# machNguyenLy.net
KiCad netlist of a schematic drawn in Altium Designer
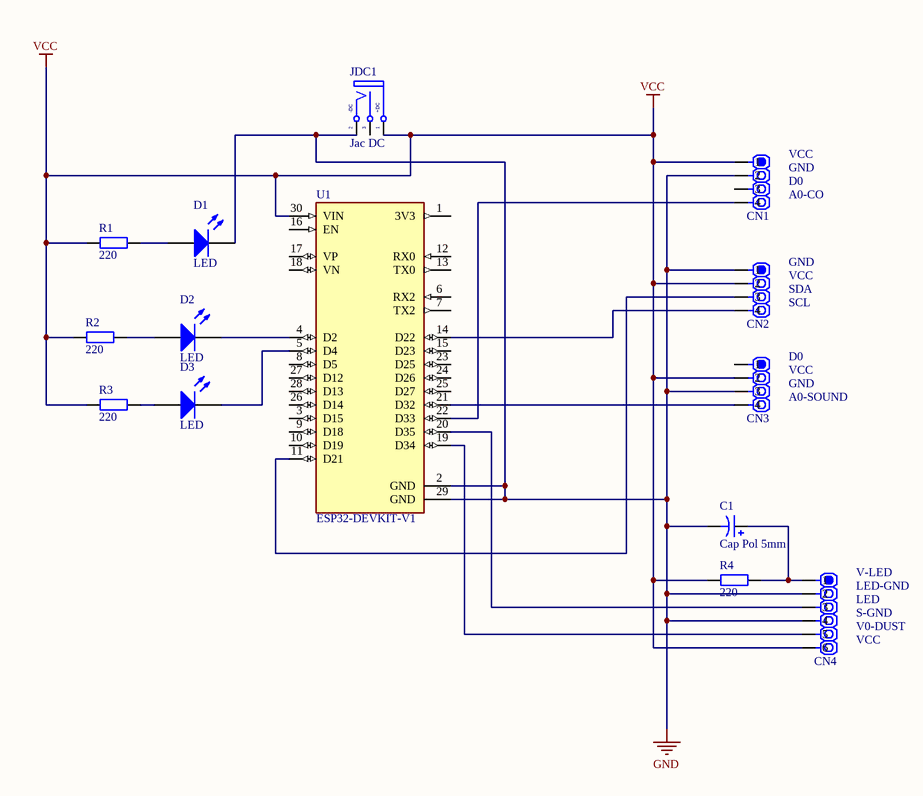
[diagram p0: machNguyenLy.SchDoc]

(export (version "E")
  (design (tool "Eeschema 10.0.6"))
  (components
    (comp (ref "C1")
      (value "Cap Pol 5mm")
      (footprint "C5mm")
      (description "Polarized Capacitor (Axial)")
      (fields (field (name "PUBLISHER") "Altium Limited"))
      (libsource (lib "hphonglib") (part "Cap Pol 5mm"))
    )
    (comp (ref "CN1")
      (value "IO")
      (footprint "CON.HDR1X4")
      (description "Header 1x4")
      (fields (field (name "PUBLISHER") "Hoang Nguyen"))
      (libsource (lib "hphonglib") (part "CON.HDR1x4"))
    )
    (comp (ref "CN2")
      (value "IO")
      (footprint "CON.HDR1X4")
      (description "Header 1x4")
      (fields (field (name "PUBLISHER") "Hoang Nguyen"))
      (libsource (lib "hphonglib") (part "CON.HDR1x4"))
    )
    (comp (ref "CN3")
      (value "IO")
      (footprint "CON.HDR1X4")
      (description "Header 1x4")
      (fields (field (name "PUBLISHER") "Hoang Nguyen"))
      (libsource (lib "hphonglib") (part "CON.HDR1x4"))
    )
    (comp (ref "CN4")
      (value "IO")
      (footprint "CON.HDR1X6")
      (description "Header 1x6")
      (fields (field (name "PUBLISHER") "Hoang Nguyen"))
      (libsource (lib "hphonglib") (part "CON.HDR1x6"))
    )
    (comp (ref "D1")
      (value "LED")
      (footprint "LED-0 5mm RED")
      (description "Typical LED")
      (fields (field (name "PUBLISHER") "Altium Limited"))
      (libsource (lib "hphonglib") (part "LED"))
    )
    (comp (ref "D2")
      (value "LED")
      (footprint "LED-0 5mm RED")
      (description "Typical LED")
      (fields (field (name "PUBLISHER") "Altium Limited"))
      (libsource (lib "hphonglib") (part "LED"))
    )
    (comp (ref "D3")
      (value "LED")
      (footprint "LED-0 5mm RED")
      (description "Typical LED")
      (fields (field (name "PUBLISHER") "Altium Limited"))
      (libsource (lib "hphonglib") (part "LED"))
    )
    (comp (ref "JDC1")
      (value "Jac DC")
      (footprint "DC-IN")
      (description "Jac DC input")
      (libsource (lib "hphonglib") (part "DCIN"))
    )
    (comp (ref "R1")
      (value "220")
      (footprint "R1/4W")
      (description "Resistor 1/4W")
      (libsource (lib "hphonglib") (part "R1/4W"))
    )
    (comp (ref "R2")
      (value "220")
      (footprint "R1/4W")
      (description "Resistor 1/4W")
      (libsource (lib "hphonglib") (part "R1/4W"))
    )
    (comp (ref "R3")
      (value "220")
      (footprint "R1/4W")
      (description "Resistor 1/4W")
      (libsource (lib "hphonglib") (part "R1/4W"))
    )
    (comp (ref "R4")
      (value "220")
      (footprint "R1/4W")
      (description "Resistor 1/4W")
      (libsource (lib "hphonglib") (part "R1/4W"))
    )
    (comp (ref "U1")
      (value "ESP32-DEVKIT-V1")
      (footprint "MODULE_ESP32_DEVKIT_V1")
      (fields (field (name "MF") "Do it"))
      (libsource (lib "ESP32-DEVKIT-V1") (part "ESP32-DEVKIT-V1"))
    )
  )
  (nets
    (net (code "1") (name "GND") (class "Default")
      (node (ref "C1") (pin "2") (pinfunction "2_2") (pintype "passive"))
      (node (ref "CN1") (pin "2") (pinfunction "2_2") (pintype "passive"))
      (node (ref "CN2") (pin "1") (pinfunction "1_1") (pintype "passive"))
      (node (ref "CN3") (pin "3") (pinfunction "3_3") (pintype "passive"))
      (node (ref "CN4") (pin "2") (pinfunction "2_2") (pintype "passive"))
      (node (ref "CN4") (pin "4") (pinfunction "4_4") (pintype "passive"))
      (node (ref "D1") (pin "2") (pinfunction "K_2") (pintype "passive"))
      (node (ref "JDC1") (pin "2") (pinfunction "TN_2") (pintype "passive"))
      (node (ref "U1") (pin "2") (pinfunction "GND_2") (pintype "power_in"))
      (node (ref "U1") (pin "29") (pinfunction "GND_29") (pintype "power_in"))
    )
    (net (code "2") (name "Net-(C1-Pad1)") (class "Default")
      (node (ref "C1") (pin "1") (pinfunction "1_1") (pintype "passive"))
      (node (ref "CN4") (pin "1") (pinfunction "1_1") (pintype "passive"))
      (node (ref "R4") (pin "2") (pinfunction "2_2") (pintype "passive"))
    )
    (net (code "3") (name "Net-(D1-A)") (class "Default")
      (node (ref "D1") (pin "1") (pinfunction "A_1") (pintype "passive"))
      (node (ref "R1") (pin "2") (pinfunction "2_2") (pintype "passive"))
    )
    (net (code "4") (name "Net-(D2-A)") (class "Default")
      (node (ref "D2") (pin "1") (pinfunction "A_1") (pintype "passive"))
      (node (ref "R2") (pin "2") (pinfunction "2_2") (pintype "passive"))
    )
    (net (code "5") (name "Net-(D2-K)") (class "Default")
      (node (ref "D2") (pin "2") (pinfunction "K_2") (pintype "passive"))
      (node (ref "U1") (pin "4") (pinfunction "D2_4") (pintype "bidirectional"))
    )
    (net (code "6") (name "Net-(D3-A)") (class "Default")
      (node (ref "D3") (pin "1") (pinfunction "A_1") (pintype "passive"))
      (node (ref "R3") (pin "2") (pinfunction "2_2") (pintype "passive"))
    )
    (net (code "7") (name "Net-(D3-K)") (class "Default")
      (node (ref "D3") (pin "2") (pinfunction "K_2") (pintype "passive"))
      (node (ref "U1") (pin "5") (pinfunction "D4_5") (pintype "bidirectional"))
    )
    (net (code "8") (name "Net-(U1-D21)") (class "Default")
      (node (ref "CN2") (pin "3") (pinfunction "3_3") (pintype "passive"))
      (node (ref "U1") (pin "11") (pinfunction "D21_11") (pintype "bidirectional"))
    )
    (net (code "9") (name "Net-(U1-D22)") (class "Default")
      (node (ref "CN2") (pin "4") (pinfunction "4_4") (pintype "passive"))
      (node (ref "U1") (pin "14") (pinfunction "D22_14") (pintype "bidirectional"))
    )
    (net (code "10") (name "Net-(U1-D32)") (class "Default")
      (node (ref "CN3") (pin "4") (pinfunction "4_4") (pintype "passive"))
      (node (ref "U1") (pin "21") (pinfunction "D32_21") (pintype "bidirectional"))
    )
    (net (code "11") (name "Net-(U1-D33)") (class "Default")
      (node (ref "CN1") (pin "4") (pinfunction "4_4") (pintype "passive"))
      (node (ref "U1") (pin "22") (pinfunction "D33_22") (pintype "bidirectional"))
    )
    (net (code "12") (name "Net-(U1-D34)") (class "Default")
      (node (ref "CN4") (pin "5") (pinfunction "5_5") (pintype "passive"))
      (node (ref "U1") (pin "19") (pinfunction "D34_19") (pintype "bidirectional"))
    )
    (net (code "13") (name "Net-(U1-D35)") (class "Default")
      (node (ref "CN4") (pin "3") (pinfunction "3_3") (pintype "passive"))
      (node (ref "U1") (pin "20") (pinfunction "D35_20") (pintype "bidirectional"))
    )
    (net (code "14") (name "VCC") (class "Default")
      (node (ref "CN1") (pin "1") (pinfunction "1_1") (pintype "passive"))
      (node (ref "CN2") (pin "2") (pinfunction "2_2") (pintype "passive"))
      (node (ref "CN3") (pin "2") (pinfunction "2_2") (pintype "passive"))
      (node (ref "CN4") (pin "6") (pinfunction "6_6") (pintype "passive"))
      (node (ref "JDC1") (pin "1") (pinfunction "T_1") (pintype "passive"))
      (node (ref "R1") (pin "1") (pinfunction "1_1") (pintype "passive"))
      (node (ref "R2") (pin "1") (pinfunction "1_1") (pintype "passive"))
      (node (ref "R3") (pin "1") (pinfunction "1_1") (pintype "passive"))
      (node (ref "R4") (pin "1") (pinfunction "1_1") (pintype "passive"))
      (node (ref "U1") (pin "30") (pinfunction "VIN_30") (pintype "input"))
    )
    (net (code "15") (name "unconnected-(CN1-Pad3)") (class "Default")
      (node (ref "CN1") (pin "3") (pinfunction "3_3") (pintype "passive"))
    )
    (net (code "16") (name "unconnected-(CN3-Pad1)") (class "Default")
      (node (ref "CN3") (pin "1") (pinfunction "1_1") (pintype "passive"))
    )
    (net (code "17") (name "unconnected-(JDC1-S-Pad3)") (class "Default")
      (node (ref "JDC1") (pin "3") (pinfunction "S_3") (pintype "power_in"))
    )
    (net (code "18") (name "unconnected-(U1-3V3-Pad1)") (class "Default")
      (node (ref "U1") (pin "1") (pinfunction "3V3_1") (pintype "output"))
    )
    (net (code "19") (name "unconnected-(U1-D5-Pad8)") (class "Default")
      (node (ref "U1") (pin "8") (pinfunction "D5_8") (pintype "bidirectional"))
    )
    (net (code "20") (name "unconnected-(U1-D12-Pad27)") (class "Default")
      (node (ref "U1") (pin "27") (pinfunction "D12_27") (pintype "bidirectional"))
    )
    (net (code "21") (name "unconnected-(U1-D13-Pad28)") (class "Default")
      (node (ref "U1") (pin "28") (pinfunction "D13_28") (pintype "bidirectional"))
    )
    (net (code "22") (name "unconnected-(U1-D14-Pad26)") (class "Default")
      (node (ref "U1") (pin "26") (pinfunction "D14_26") (pintype "bidirectional"))
    )
    (net (code "23") (name "unconnected-(U1-D15-Pad3)") (class "Default")
      (node (ref "U1") (pin "3") (pinfunction "D15_3") (pintype "bidirectional"))
    )
    (net (code "24") (name "unconnected-(U1-D18-Pad9)") (class "Default")
      (node (ref "U1") (pin "9") (pinfunction "D18_9") (pintype "bidirectional"))
    )
    (net (code "25") (name "unconnected-(U1-D19-Pad10)") (class "Default")
      (node (ref "U1") (pin "10") (pinfunction "D19_10") (pintype "bidirectional"))
    )
    (net (code "26") (name "unconnected-(U1-D23-Pad15)") (class "Default")
      (node (ref "U1") (pin "15") (pinfunction "D23_15") (pintype "bidirectional"))
    )
    (net (code "27") (name "unconnected-(U1-D25-Pad23)") (class "Default")
      (node (ref "U1") (pin "23") (pinfunction "D25_23") (pintype "bidirectional"))
    )
    (net (code "28") (name "unconnected-(U1-D26-Pad24)") (class "Default")
      (node (ref "U1") (pin "24") (pinfunction "D26_24") (pintype "bidirectional"))
    )
    (net (code "29") (name "unconnected-(U1-D27-Pad25)") (class "Default")
      (node (ref "U1") (pin "25") (pinfunction "D27_25") (pintype "bidirectional"))
    )
    (net (code "30") (name "unconnected-(U1-EN-Pad16)") (class "Default")
      (node (ref "U1") (pin "16") (pinfunction "EN_16") (pintype "input"))
    )
    (net (code "31") (name "unconnected-(U1-RX0-Pad12)") (class "Default")
      (node (ref "U1") (pin "12") (pinfunction "RX0_12") (pintype "input"))
    )
    (net (code "32") (name "unconnected-(U1-RX2-Pad6)") (class "Default")
      (node (ref "U1") (pin "6") (pinfunction "RX2_6") (pintype "input"))
    )
    (net (code "33") (name "unconnected-(U1-TX0-Pad13)") (class "Default")
      (node (ref "U1") (pin "13") (pinfunction "TX0_13") (pintype "output"))
    )
    (net (code "34") (name "unconnected-(U1-TX2-Pad7)") (class "Default")
      (node (ref "U1") (pin "7") (pinfunction "TX2_7") (pintype "output"))
    )
    (net (code "35") (name "unconnected-(U1-VN-Pad18)") (class "Default")
      (node (ref "U1") (pin "18") (pinfunction "VN_18") (pintype "bidirectional"))
    )
    (net (code "36") (name "unconnected-(U1-VP-Pad17)") (class "Default")
      (node (ref "U1") (pin "17") (pinfunction "VP_17") (pintype "bidirectional"))
    )
  )
)
